# scrump.net
KiCad netlist of a schematic drawn in EAGLE
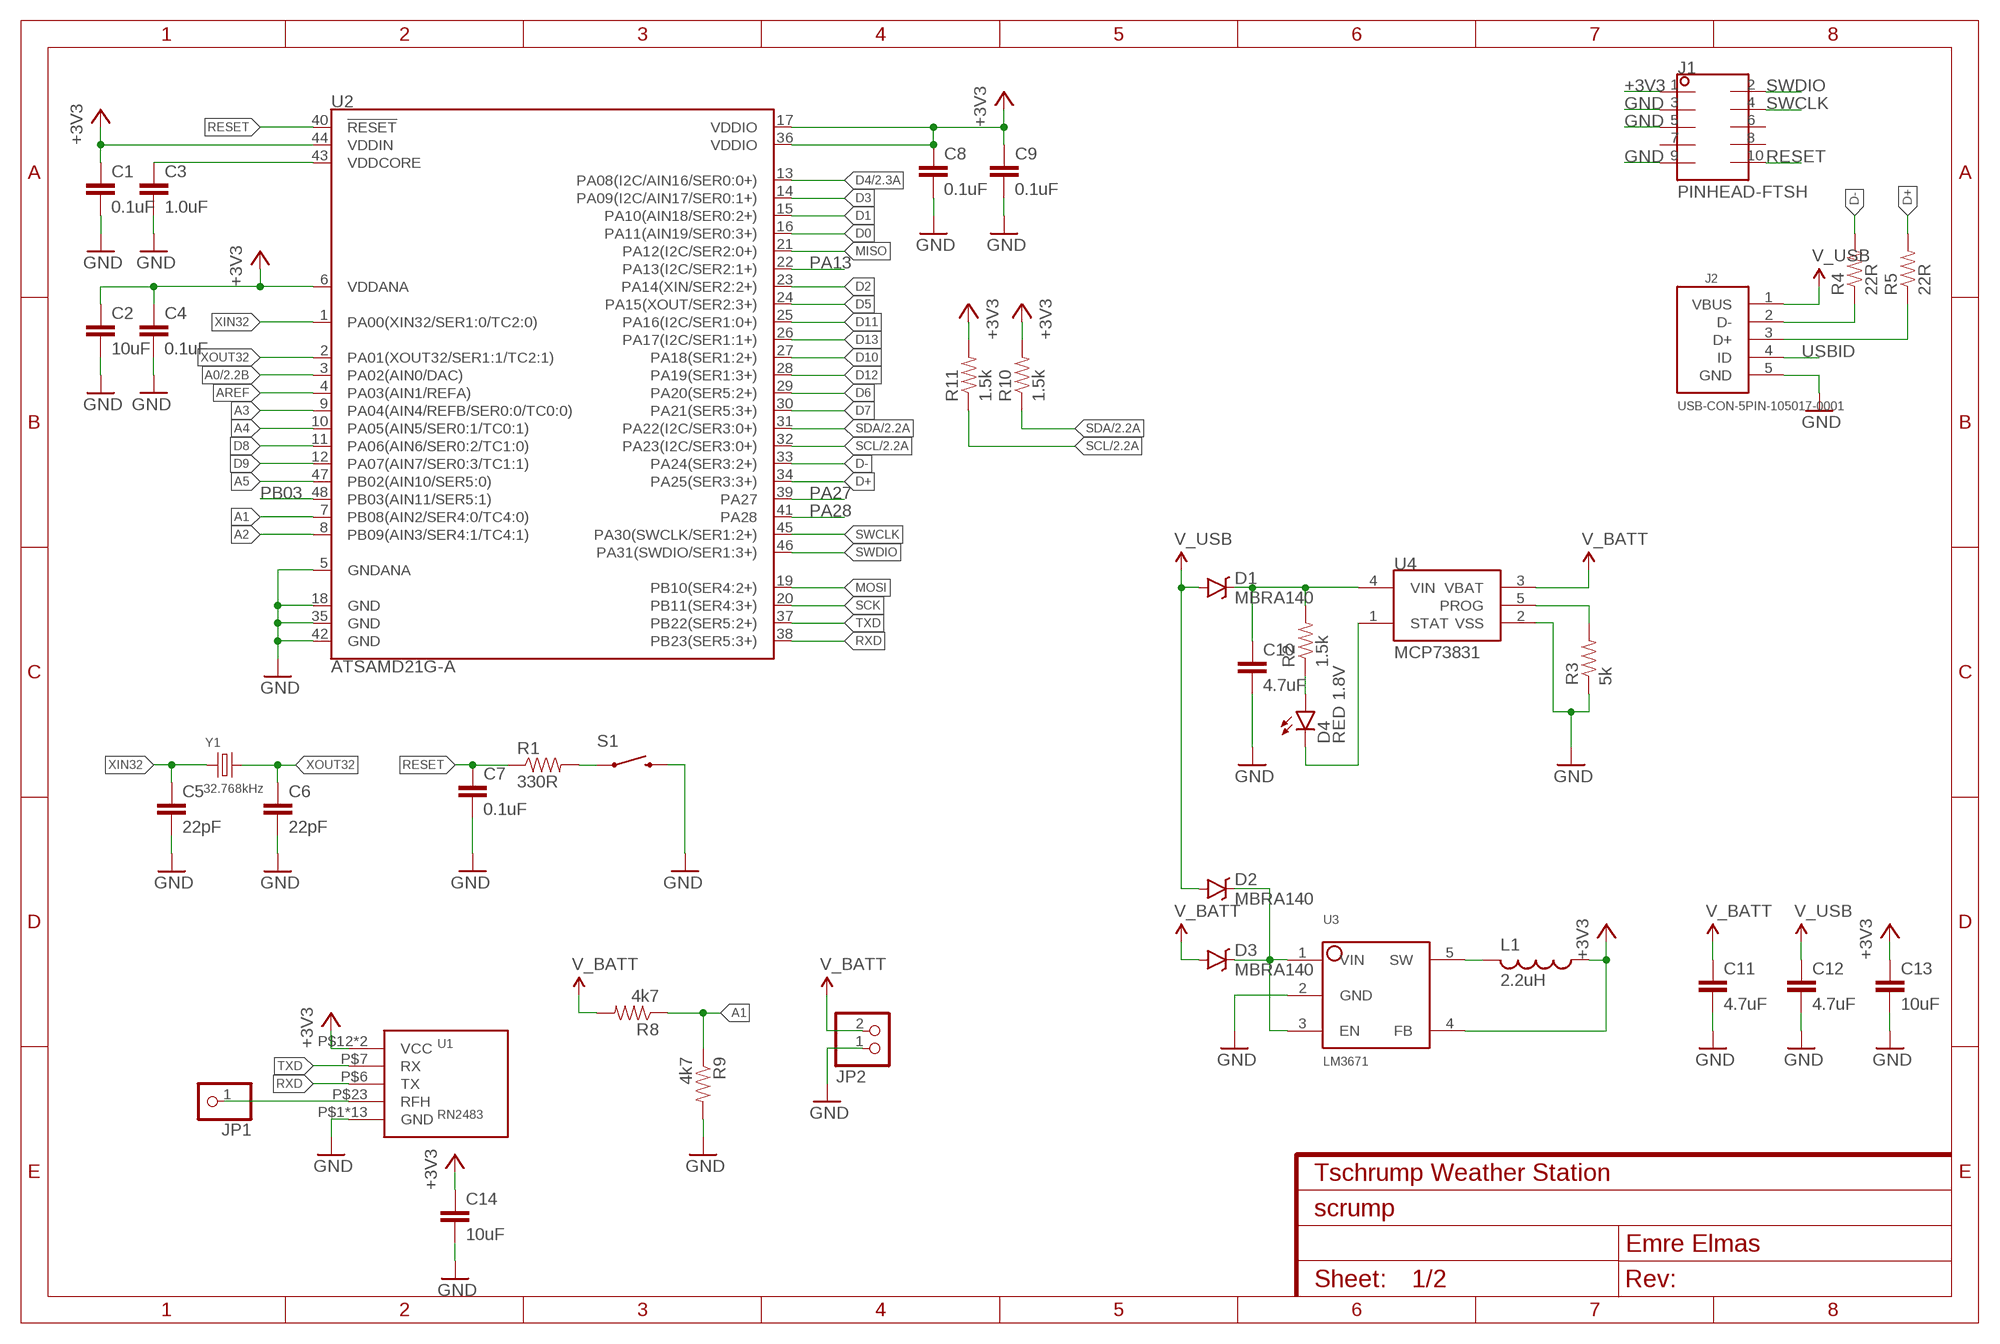
[diagram p0: schematic, sheet 1]
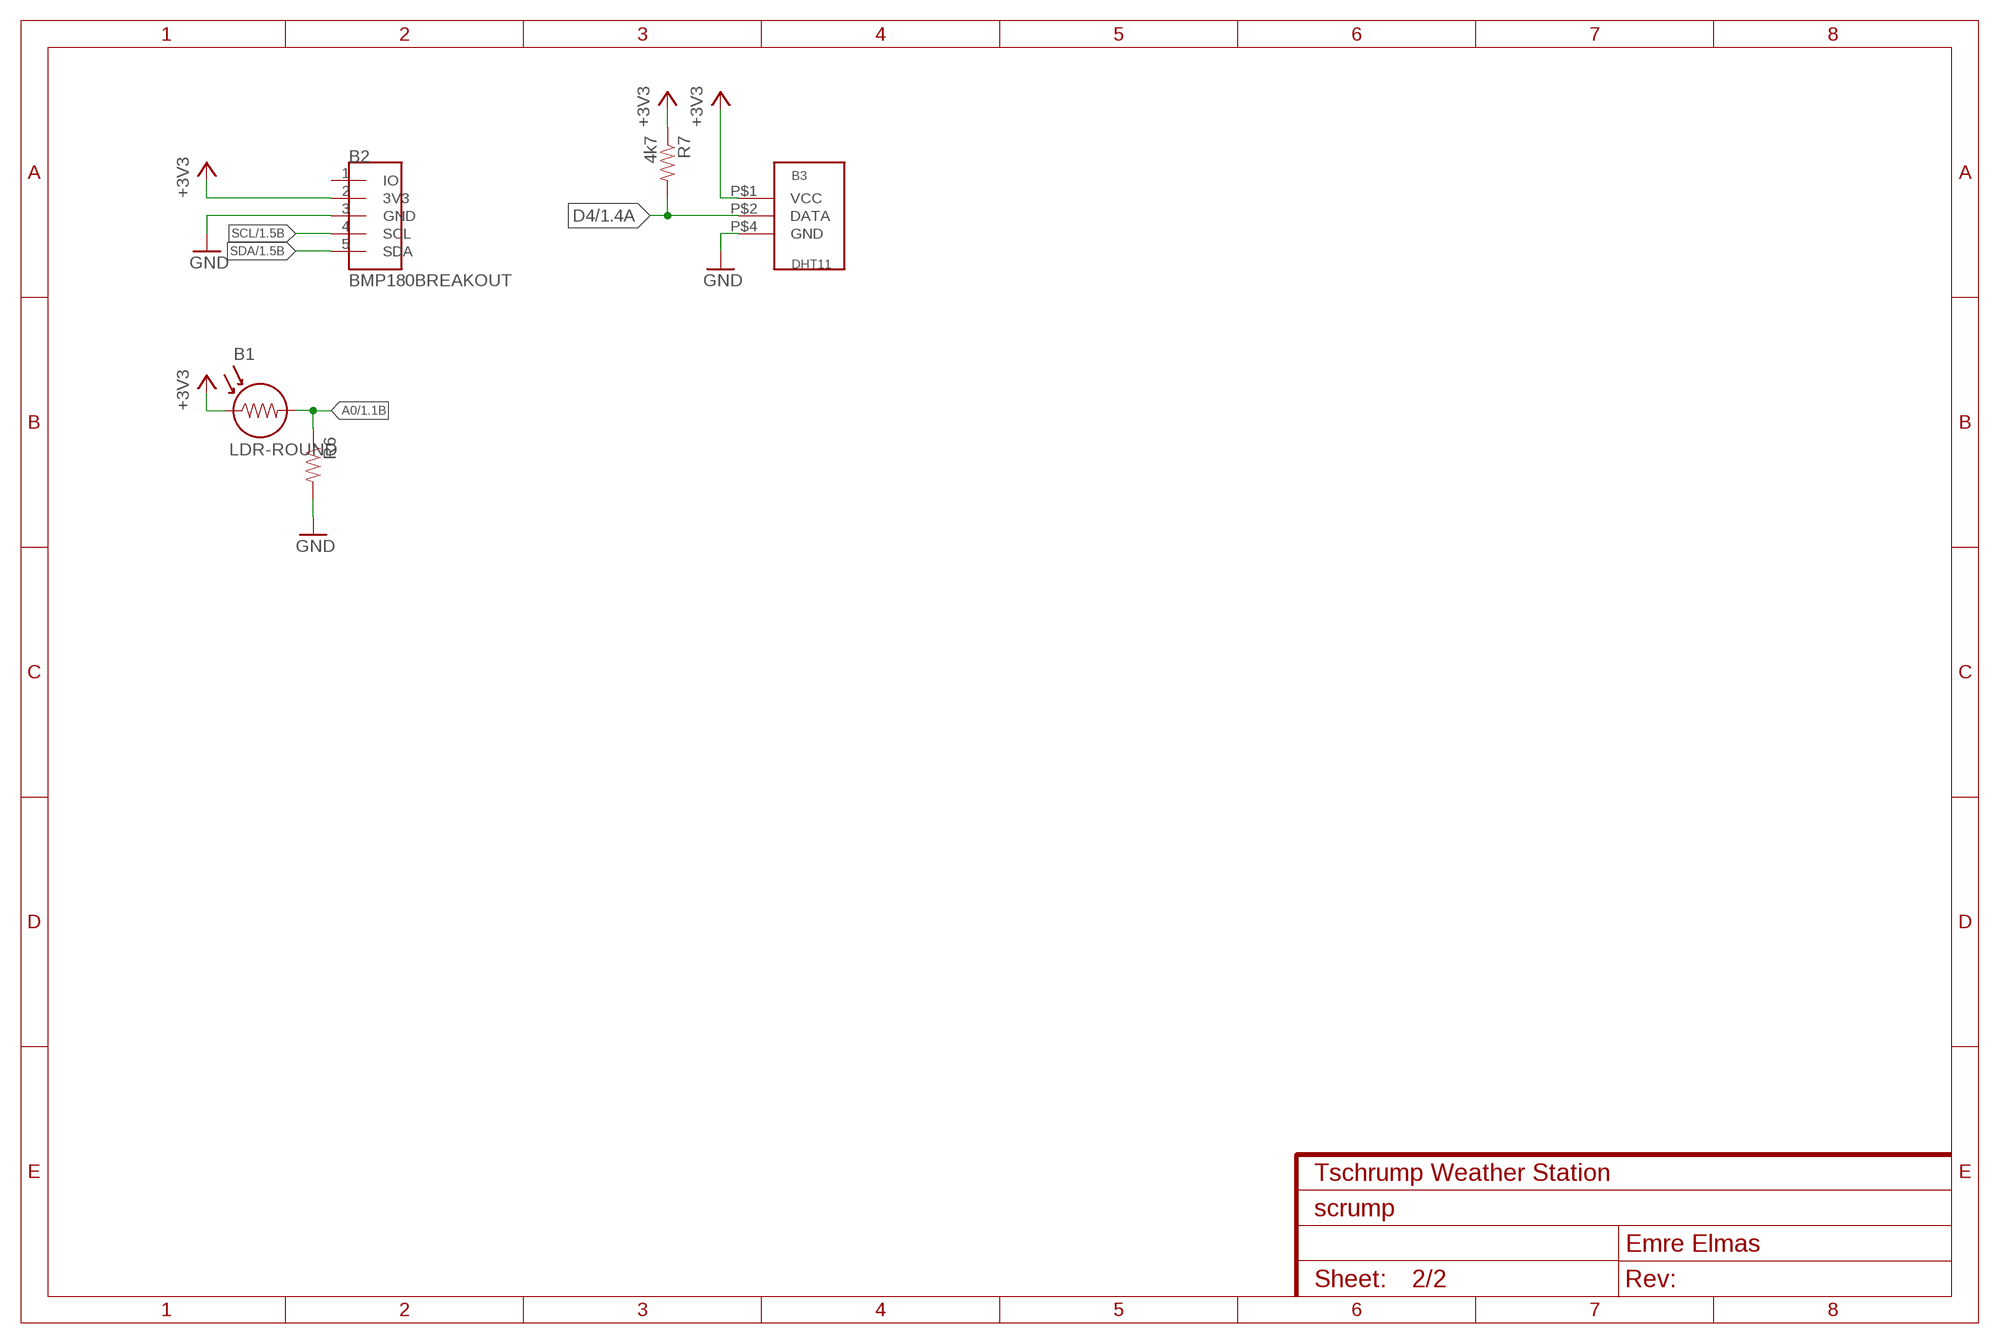
[diagram p1: schematic, sheet 2]

(export (version "E")
  (design (tool "Eeschema 10.0.6"))
  (components
    (comp (ref "B1")
      (value "LDR-ROUND")
      (footprint "eagle-import:LDR-ROUND")
      (libsource (lib "eagle-import") (part "LDR-ROUND"))
    )
    (comp (ref "B2")
      (value "BMP180BREAKOUT")
      (footprint "eagle-import:BMP180_BREAKOUT")
      (libsource (lib "eagle-import") (part "BMP180BREAKOUT"))
    )
    (comp (ref "B3")
      (value "DHT11")
      (footprint "eagle-import:DHT11")
      (libsource (lib "eagle-import") (part "DHT11"))
    )
    (comp (ref "R6")
      (value "RESISTOR0603")
      (footprint "eagle-import:0603-RES")
      (libsource (lib "eagle-import") (part "RESISTOR0603"))
    )
    (comp (ref "R7")
      (value "4k7")
      (footprint "eagle-import:0603-RES")
      (libsource (lib "eagle-import") (part "RESISTOR0603"))
    )
    (comp (ref "C1")
      (value "0.1uF")
      (footprint "eagle-import:0603-CAP")
      (libsource (lib "eagle-import") (part "CAP0603-CAP"))
    )
    (comp (ref "C2")
      (value "10uF")
      (footprint "eagle-import:0603-CAP")
      (libsource (lib "eagle-import") (part "CAP0603-CAP"))
    )
    (comp (ref "C3")
      (value "1.0uF")
      (footprint "eagle-import:0603-CAP")
      (libsource (lib "eagle-import") (part "CAP0603-CAP"))
    )
    (comp (ref "C4")
      (value "0.1uF")
      (footprint "eagle-import:0603-CAP")
      (libsource (lib "eagle-import") (part "CAP0603-CAP"))
    )
    (comp (ref "C5")
      (value "22pF")
      (footprint "eagle-import:0603-CAP")
      (libsource (lib "eagle-import") (part "CAP0603-CAP"))
    )
    (comp (ref "C6")
      (value "22pF")
      (footprint "eagle-import:0603-CAP")
      (libsource (lib "eagle-import") (part "CAP0603-CAP"))
    )
    (comp (ref "C7")
      (value "0.1uF")
      (footprint "eagle-import:0603-CAP")
      (libsource (lib "eagle-import") (part "0.1UF-25V(+80/-20%)(0603)"))
    )
    (comp (ref "C8")
      (value "0.1uF")
      (footprint "eagle-import:0603-CAP")
      (libsource (lib "eagle-import") (part "CAP0603-CAP"))
    )
    (comp (ref "C9")
      (value "0.1uF")
      (footprint "eagle-import:0603-CAP")
      (libsource (lib "eagle-import") (part "CAP0603-CAP"))
    )
    (comp (ref "C10")
      (value "4.7uF")
      (footprint "eagle-import:0603-CAP")
      (libsource (lib "eagle-import") (part "CAP0603-CAP"))
    )
    (comp (ref "C11")
      (value "4.7uF")
      (footprint "eagle-import:0603-CAP")
      (libsource (lib "eagle-import") (part "CAP0603-CAP"))
    )
    (comp (ref "C12")
      (value "4.7uF")
      (footprint "eagle-import:0603-CAP")
      (libsource (lib "eagle-import") (part "CAP0603-CAP"))
    )
    (comp (ref "C13")
      (value "10uF")
      (footprint "eagle-import:0603-CAP")
      (libsource (lib "eagle-import") (part "CAP0603-CAP"))
    )
    (comp (ref "C14")
      (value "10uF")
      (footprint "eagle-import:0603-CAP")
      (libsource (lib "eagle-import") (part "CAP0603-CAP"))
    )
    (comp (ref "D1")
      (value "MBRA140")
      (footprint "eagle-import:SMA-DIODE")
      (libsource (lib "eagle-import") (part "MBRA140"))
    )
    (comp (ref "D2")
      (value "MBRA140")
      (footprint "eagle-import:SMA-DIODE")
      (libsource (lib "eagle-import") (part "MBRA140"))
    )
    (comp (ref "D3")
      (value "MBRA140")
      (footprint "eagle-import:SMA-DIODE")
      (libsource (lib "eagle-import") (part "MBRA140"))
    )
    (comp (ref "D4")
      (value "RED 1.8V")
      (footprint "eagle-import:LED-0603")
      (libsource (lib "eagle-import") (part "LED-RED0603"))
    )
    (comp (ref "J1")
      (value "PINHEAD-FTSH")
      (footprint "eagle-import:FTSH-105-01-XXX-DV-K")
      (libsource (lib "eagle-import") (part "PINHEAD-FTSH"))
    )
    (comp (ref "J2")
      (value "USB-CON-5PIN-105017-0001")
      (footprint "eagle-import:USB-MICRO-MOLEX-105017-0001")
      (libsource (lib "eagle-import") (part "USB-CON-5PIN-105017-0001"))
    )
    (comp (ref "JP1")
      (value "PINHD-1X1")
      (footprint "eagle-import:1X01")
      (libsource (lib "eagle-import") (part "PINHD-1X1"))
    )
    (comp (ref "JP2")
      (value "PINHD-1X2")
      (footprint "eagle-import:1X02")
      (libsource (lib "eagle-import") (part "PINHD-1X2"))
    )
    (comp (ref "L1")
      (value "2.2uH")
      (footprint "eagle-import:0806-INDUCTOR")
      (libsource (lib "eagle-import") (part "INDUCTOR"))
    )
    (comp (ref "R1")
      (value "330R")
      (footprint "eagle-import:0603-RES")
      (libsource (lib "eagle-import") (part "RESISTOR0603"))
    )
    (comp (ref "R2")
      (value "1.5k")
      (footprint "eagle-import:0603-RES")
      (libsource (lib "eagle-import") (part "RESISTOR0603"))
    )
    (comp (ref "R3")
      (value "5k")
      (footprint "eagle-import:0603-RES")
      (libsource (lib "eagle-import") (part "RESISTOR0603"))
    )
    (comp (ref "R4")
      (value "22R")
      (footprint "eagle-import:0603-RES")
      (libsource (lib "eagle-import") (part "RESISTOR0603"))
    )
    (comp (ref "R5")
      (value "22R")
      (footprint "eagle-import:0603-RES")
      (libsource (lib "eagle-import") (part "RESISTOR0603"))
    )
    (comp (ref "R8")
      (value "4k7")
      (footprint "eagle-import:0603-RES")
      (libsource (lib "eagle-import") (part "RESISTOR0603"))
    )
    (comp (ref "R9")
      (value "4k7")
      (footprint "eagle-import:0603-RES")
      (libsource (lib "eagle-import") (part "RESISTOR0603"))
    )
    (comp (ref "R10")
      (value "1.5k")
      (footprint "eagle-import:0603-RES")
      (libsource (lib "eagle-import") (part "RESISTOR0603"))
    )
    (comp (ref "R11")
      (value "1.5k")
      (footprint "eagle-import:0603-RES")
      (libsource (lib "eagle-import") (part "RESISTOR0603"))
    )
    (comp (ref "S1")
      (value "PUSHBUTTON-SMD")
      (footprint "eagle-import:TACTILE-SMD-SWITCH")
      (libsource (lib "eagle-import") (part "PUSHBUTTON-SMD"))
    )
    (comp (ref "U1")
      (value "RN2483")
      (footprint "eagle-import:RN2483")
      (libsource (lib "eagle-import") (part "RN2483"))
    )
    (comp (ref "U2")
      (value "ATSAMD21G-A")
      (footprint "eagle-import:TQFP-48")
      (libsource (lib "eagle-import") (part "ATSAMD21G-A"))
    )
    (comp (ref "U3")
      (value "LM3671")
      (footprint "eagle-import:SOT23-5")
      (libsource (lib "eagle-import") (part "LM3671"))
    )
    (comp (ref "U4")
      (value "MCP73831")
      (footprint "eagle-import:SOT23-5")
      (libsource (lib "eagle-import") (part "MCP73831"))
    )
    (comp (ref "Y1")
      (value "32.768kHz")
      (footprint "eagle-import:ABS25")
      (libsource (lib "eagle-import") (part "CRYSTAL"))
    )
  )
  (nets
    (net (code "1") (name "+3V3") (class "Default")
      (node (ref "B1") (pin "P$1") (pinfunction "1_P$1") (pintype "passive"))
      (node (ref "B2") (pin "2") (pinfunction "3V3_2") (pintype "bidirectional"))
      (node (ref "B3") (pin "P$1") (pinfunction "VCC_P$1") (pintype "bidirectional"))
      (node (ref "C1") (pin "1") (pinfunction "1_1") (pintype "passive"))
      (node (ref "C13") (pin "1") (pinfunction "1_1") (pintype "passive"))
      (node (ref "C14") (pin "1") (pinfunction "1_1") (pintype "passive"))
      (node (ref "C2") (pin "1") (pinfunction "1_1") (pintype "passive"))
      (node (ref "C4") (pin "1") (pinfunction "1_1") (pintype "passive"))
      (node (ref "C8") (pin "1") (pinfunction "1_1") (pintype "passive"))
      (node (ref "C9") (pin "1") (pinfunction "1_1") (pintype "passive"))
      (node (ref "J1") (pin "1") (pinfunction "P$1_1") (pintype "bidirectional"))
      (node (ref "L1") (pin "1") (pinfunction "1_1") (pintype "passive"))
      (node (ref "R10") (pin "2") (pinfunction "2_2") (pintype "passive"))
      (node (ref "R11") (pin "2") (pinfunction "2_2") (pintype "passive"))
      (node (ref "R7") (pin "1") (pinfunction "1_1") (pintype "passive"))
      (node (ref "U1") (pin "P$12") (pinfunction "VCC_P$12") (pintype "bidirectional"))
      (node (ref "U1") (pin "P$34") (pinfunction "VCC_P$34") (pintype "bidirectional"))
      (node (ref "U2") (pin "17") (pinfunction "VDDIO_17") (pintype "bidirectional"))
      (node (ref "U2") (pin "36") (pinfunction "VDDIO_36") (pintype "bidirectional"))
      (node (ref "U2") (pin "44") (pinfunction "VDDIN_44") (pintype "bidirectional"))
      (node (ref "U2") (pin "6") (pinfunction "VDDANA_6") (pintype "bidirectional"))
      (node (ref "U3") (pin "4") (pinfunction "FB_4") (pintype "bidirectional"))
    )
    (net (code "2") (name "A0") (class "Default")
      (node (ref "B1") (pin "P$2") (pinfunction "2_P$2") (pintype "passive"))
      (node (ref "R6") (pin "1") (pinfunction "1_1") (pintype "passive"))
      (node (ref "U2") (pin "3") (pinfunction "PA02(AIN0/DAC)_3") (pintype "bidirectional"))
    )
    (net (code "3") (name "A1") (class "Default")
      (node (ref "R8") (pin "1") (pinfunction "1_1") (pintype "passive"))
      (node (ref "R9") (pin "1") (pinfunction "1_1") (pintype "passive"))
      (node (ref "U2") (pin "7") (pinfunction "PB08(AIN2/SER4:0/TC4:0)_7") (pintype "bidirectional"))
    )
    (net (code "4") (name "A2") (class "Default")
      (node (ref "U2") (pin "8") (pinfunction "PB09(AIN3/SER4:1/TC4:1)_8") (pintype "bidirectional"))
    )
    (net (code "5") (name "A3") (class "Default")
      (node (ref "U2") (pin "9") (pinfunction "PA04(AIN4/REFB/SER0:0/TC0:0)_9") (pintype "bidirectional"))
    )
    (net (code "6") (name "A4") (class "Default")
      (node (ref "U2") (pin "10") (pinfunction "PA05(AIN5/SER0:1/TC0:1)_10") (pintype "bidirectional"))
    )
    (net (code "7") (name "A5") (class "Default")
      (node (ref "U2") (pin "47") (pinfunction "PB02(AIN10/SER5:0)_47") (pintype "bidirectional"))
    )
    (net (code "8") (name "AREF") (class "Default")
      (node (ref "U2") (pin "4") (pinfunction "PA03(AIN1/REFA)_4") (pintype "bidirectional"))
    )
    (net (code "9") (name "D+") (class "Default")
      (node (ref "R5") (pin "2") (pinfunction "2_2") (pintype "passive"))
      (node (ref "U2") (pin "34") (pinfunction "PA25(SER3:3+)_34") (pintype "bidirectional"))
    )
    (net (code "10") (name "D-") (class "Default")
      (node (ref "R4") (pin "2") (pinfunction "2_2") (pintype "passive"))
      (node (ref "U2") (pin "33") (pinfunction "PA24(SER3:2+)_33") (pintype "bidirectional"))
    )
    (net (code "11") (name "D0") (class "Default")
      (node (ref "U2") (pin "16") (pinfunction "PA11(AIN19/SER0:3+)_16") (pintype "bidirectional"))
    )
    (net (code "12") (name "D1") (class "Default")
      (node (ref "U2") (pin "15") (pinfunction "PA10(AIN18/SER0:2+)_15") (pintype "bidirectional"))
    )
    (net (code "13") (name "D2") (class "Default")
      (node (ref "U2") (pin "23") (pinfunction "PA14(XIN/SER2:2+)_23") (pintype "bidirectional"))
    )
    (net (code "14") (name "D3") (class "Default")
      (node (ref "U2") (pin "14") (pinfunction "PA09(I2C/AIN17/SER0:1+)_14") (pintype "bidirectional"))
    )
    (net (code "15") (name "D4") (class "Default")
      (node (ref "B3") (pin "P$2") (pinfunction "DATA_P$2") (pintype "bidirectional"))
      (node (ref "R7") (pin "2") (pinfunction "2_2") (pintype "passive"))
      (node (ref "U2") (pin "13") (pinfunction "PA08(I2C/AIN16/SER0:0+)_13") (pintype "bidirectional"))
    )
    (net (code "16") (name "D5") (class "Default")
      (node (ref "U2") (pin "24") (pinfunction "PA15(XOUT/SER2:3+)_24") (pintype "bidirectional"))
    )
    (net (code "17") (name "D6") (class "Default")
      (node (ref "U2") (pin "29") (pinfunction "PA20(SER5:2+)_29") (pintype "bidirectional"))
    )
    (net (code "18") (name "D7") (class "Default")
      (node (ref "U2") (pin "30") (pinfunction "PA21(SER5:3+)_30") (pintype "bidirectional"))
    )
    (net (code "19") (name "D8") (class "Default")
      (node (ref "U2") (pin "11") (pinfunction "PA06(AIN6/SER0:2/TC1:0)_11") (pintype "bidirectional"))
    )
    (net (code "20") (name "D9") (class "Default")
      (node (ref "U2") (pin "12") (pinfunction "PA07(AIN7/SER0:3/TC1:1)_12") (pintype "bidirectional"))
    )
    (net (code "21") (name "D10") (class "Default")
      (node (ref "U2") (pin "27") (pinfunction "PA18(SER1:2+)_27") (pintype "bidirectional"))
    )
    (net (code "22") (name "D11") (class "Default")
      (node (ref "U2") (pin "25") (pinfunction "PA16(I2C/SER1:0+)_25") (pintype "bidirectional"))
    )
    (net (code "23") (name "D12") (class "Default")
      (node (ref "U2") (pin "28") (pinfunction "PA19(SER1:3+)_28") (pintype "bidirectional"))
    )
    (net (code "24") (name "D13") (class "Default")
      (node (ref "U2") (pin "26") (pinfunction "PA17(I2C/SER1:1+)_26") (pintype "bidirectional"))
    )
    (net (code "25") (name "GND") (class "Default")
      (node (ref "B2") (pin "3") (pinfunction "GND_3") (pintype "bidirectional"))
      (node (ref "B3") (pin "P$4") (pinfunction "GND_P$4") (pintype "bidirectional"))
      (node (ref "C1") (pin "2") (pinfunction "2_2") (pintype "passive"))
      (node (ref "C10") (pin "2") (pinfunction "2_2") (pintype "passive"))
      (node (ref "C11") (pin "2") (pinfunction "2_2") (pintype "passive"))
      (node (ref "C12") (pin "2") (pinfunction "2_2") (pintype "passive"))
      (node (ref "C13") (pin "2") (pinfunction "2_2") (pintype "passive"))
      (node (ref "C14") (pin "2") (pinfunction "2_2") (pintype "passive"))
      (node (ref "C2") (pin "2") (pinfunction "2_2") (pintype "passive"))
      (node (ref "C3") (pin "2") (pinfunction "2_2") (pintype "passive"))
      (node (ref "C4") (pin "2") (pinfunction "2_2") (pintype "passive"))
      (node (ref "C5") (pin "2") (pinfunction "2_2") (pintype "passive"))
      (node (ref "C6") (pin "2") (pinfunction "2_2") (pintype "passive"))
      (node (ref "C7") (pin "2") (pinfunction "2_2") (pintype "passive"))
      (node (ref "C8") (pin "2") (pinfunction "2_2") (pintype "passive"))
      (node (ref "C9") (pin "2") (pinfunction "2_2") (pintype "passive"))
      (node (ref "J1") (pin "3") (pinfunction "P$3_3") (pintype "bidirectional"))
      (node (ref "J1") (pin "5") (pinfunction "P$5_5") (pintype "bidirectional"))
      (node (ref "J1") (pin "9") (pinfunction "P$9_9") (pintype "bidirectional"))
      (node (ref "J2") (pin "5") (pinfunction "GND_5") (pintype "power_in"))
      (node (ref "JP2") (pin "1") (pinfunction "1_1") (pintype "passive"))
      (node (ref "R3") (pin "1") (pinfunction "1_1") (pintype "passive"))
      (node (ref "R6") (pin "2") (pinfunction "2_2") (pintype "passive"))
      (node (ref "R9") (pin "2") (pinfunction "2_2") (pintype "passive"))
      (node (ref "S1") (pin "P$3") (pinfunction "2_P$3") (pintype "passive"))
      (node (ref "S1") (pin "P$4") (pinfunction "2_P$4") (pintype "passive"))
      (node (ref "U1") (pin "P$1") (pinfunction "GND_P$1") (pintype "bidirectional"))
      (node (ref "U1") (pin "P$11") (pinfunction "GND_P$11") (pintype "bidirectional"))
      (node (ref "U1") (pin "P$20") (pinfunction "GND_P$20") (pintype "bidirectional"))
      (node (ref "U1") (pin "P$21") (pinfunction "GND_P$21") (pintype "bidirectional"))
      (node (ref "U1") (pin "P$22") (pinfunction "GND_P$22") (pintype "bidirectional"))
      (node (ref "U1") (pin "P$24") (pinfunction "GND_P$24") (pintype "bidirectional"))
      (node (ref "U1") (pin "P$26") (pinfunction "GND_P$26") (pintype "bidirectional"))
      (node (ref "U1") (pin "P$27") (pinfunction "GND_P$27") (pintype "bidirectional"))
      (node (ref "U1") (pin "P$28") (pinfunction "GND_P$28") (pintype "bidirectional"))
      (node (ref "U1") (pin "P$33") (pinfunction "GND_P$33") (pintype "bidirectional"))
      (node (ref "U1") (pin "P$41") (pinfunction "GND_P$41") (pintype "bidirectional"))
      (node (ref "U1") (pin "P$47") (pinfunction "GND_P$47") (pintype "bidirectional"))
      (node (ref "U1") (pin "P$8") (pinfunction "GND_P$8") (pintype "bidirectional"))
      (node (ref "U2") (pin "18") (pinfunction "GND_18") (pintype "bidirectional"))
      (node (ref "U2") (pin "35") (pinfunction "GND_35") (pintype "bidirectional"))
      (node (ref "U2") (pin "42") (pinfunction "GND_42") (pintype "bidirectional"))
      (node (ref "U2") (pin "5") (pinfunction "GNDANA_5") (pintype "bidirectional"))
      (node (ref "U3") (pin "2") (pinfunction "GND_2") (pintype "bidirectional"))
      (node (ref "U4") (pin "2") (pinfunction "VSS_2") (pintype "bidirectional"))
    )
    (net (code "26") (name "MISO") (class "Default")
      (node (ref "U2") (pin "21") (pinfunction "PA12(I2C/SER2:0+)_21") (pintype "bidirectional"))
    )
    (net (code "27") (name "MOSI") (class "Default")
      (node (ref "U2") (pin "19") (pinfunction "PB10(SER4:2+)_19") (pintype "bidirectional"))
    )
    (net (code "28") (name "Net-(D4-PadA)") (class "Default")
      (node (ref "D4") (pin "A") (pinfunction "A_A") (pintype "passive"))
      (node (ref "R2") (pin "1") (pinfunction "1_1") (pintype "passive"))
    )
    (net (code "29") (name "Net-(J2-D+)") (class "Default")
      (node (ref "J2") (pin "3") (pinfunction "D+_3") (pintype "bidirectional"))
      (node (ref "R5") (pin "1") (pinfunction "1_1") (pintype "passive"))
    )
    (net (code "30") (name "Net-(J2-D-)") (class "Default")
      (node (ref "J2") (pin "2") (pinfunction "D-_2") (pintype "bidirectional"))
      (node (ref "R4") (pin "1") (pinfunction "1_1") (pintype "passive"))
    )
    (net (code "31") (name "Net-(R1-Pad2)") (class "Default")
      (node (ref "R1") (pin "2") (pinfunction "2_2") (pintype "passive"))
      (node (ref "S1") (pin "P$1") (pinfunction "1_P$1") (pintype "passive"))
      (node (ref "S1") (pin "P$2") (pinfunction "1_P$2") (pintype "passive"))
    )
    (net (code "32") (name "Net-(U1-RFH)") (class "Default")
      (node (ref "JP1") (pin "1") (pinfunction "1_1") (pintype "passive"))
      (node (ref "U1") (pin "P$23") (pinfunction "RFH_P$23") (pintype "bidirectional"))
    )
    (net (code "33") (name "Net-(U2-VDDCORE)") (class "Default")
      (node (ref "C3") (pin "1") (pinfunction "1_1") (pintype "passive"))
      (node (ref "U2") (pin "43") (pinfunction "VDDCORE_43") (pintype "bidirectional"))
    )
    (net (code "34") (name "Net-(U3-EN)") (class "Default")
      (node (ref "D2") (pin "C") (pinfunction "C_C") (pintype "passive"))
      (node (ref "D3") (pin "C") (pinfunction "C_C") (pintype "passive"))
      (node (ref "U3") (pin "1") (pinfunction "VIN_1") (pintype "bidirectional"))
      (node (ref "U3") (pin "3") (pinfunction "EN_3") (pintype "bidirectional"))
    )
    (net (code "35") (name "Net-(U3-SW)") (class "Default")
      (node (ref "L1") (pin "2") (pinfunction "2_2") (pintype "passive"))
      (node (ref "U3") (pin "5") (pinfunction "SW_5") (pintype "bidirectional"))
    )
    (net (code "36") (name "Net-(U4-PROG)") (class "Default")
      (node (ref "R3") (pin "2") (pinfunction "2_2") (pintype "passive"))
      (node (ref "U4") (pin "5") (pinfunction "PROG_5") (pintype "bidirectional"))
    )
    (net (code "37") (name "Net-(U4-STAT)") (class "Default")
      (node (ref "D4") (pin "C") (pinfunction "C_C") (pintype "passive"))
      (node (ref "U4") (pin "1") (pinfunction "STAT_1") (pintype "bidirectional"))
    )
    (net (code "38") (name "Net-(U4-VIN)") (class "Default")
      (node (ref "C10") (pin "1") (pinfunction "1_1") (pintype "passive"))
      (node (ref "D1") (pin "C") (pinfunction "C_C") (pintype "passive"))
      (node (ref "R2") (pin "2") (pinfunction "2_2") (pintype "passive"))
      (node (ref "U4") (pin "4") (pinfunction "VIN_4") (pintype "bidirectional"))
    )
    (net (code "39") (name "PA13") (class "Default")
      (node (ref "U2") (pin "22") (pinfunction "PA13(I2C/SER2:1+)_22") (pintype "bidirectional"))
    )
    (net (code "40") (name "PA27") (class "Default")
      (node (ref "U2") (pin "39") (pinfunction "PA27_39") (pintype "bidirectional"))
    )
    (net (code "41") (name "PA28") (class "Default")
      (node (ref "U2") (pin "41") (pinfunction "PA28_41") (pintype "bidirectional"))
    )
    (net (code "42") (name "PB03") (class "Default")
      (node (ref "U2") (pin "48") (pinfunction "PB03(AIN11/SER5:1)_48") (pintype "bidirectional"))
    )
    (net (code "43") (name "RESET") (class "Default")
      (node (ref "C7") (pin "1") (pinfunction "1_1") (pintype "passive"))
      (node (ref "J1") (pin "10") (pinfunction "P$10_10") (pintype "bidirectional"))
      (node (ref "R1") (pin "1") (pinfunction "1_1") (pintype "passive"))
      (node (ref "U2") (pin "40") (pinfunction "~{RESET}_40") (pintype "bidirectional"))
    )
    (net (code "44") (name "RXD") (class "Default")
      (node (ref "U1") (pin "P$6") (pinfunction "TX_P$6") (pintype "bidirectional"))
      (node (ref "U2") (pin "38") (pinfunction "PB23(SER5:3+)_38") (pintype "bidirectional"))
    )
    (net (code "45") (name "SCK") (class "Default")
      (node (ref "U2") (pin "20") (pinfunction "PB11(SER4:3+)_20") (pintype "bidirectional"))
    )
    (net (code "46") (name "SCL") (class "Default")
      (node (ref "B2") (pin "4") (pinfunction "SCL_4") (pintype "bidirectional"))
      (node (ref "R11") (pin "1") (pinfunction "1_1") (pintype "passive"))
      (node (ref "U2") (pin "32") (pinfunction "PA23(I2C/SER3:0+)_32") (pintype "bidirectional"))
    )
    (net (code "47") (name "SDA") (class "Default")
      (node (ref "B2") (pin "5") (pinfunction "SDA_5") (pintype "bidirectional"))
      (node (ref "R10") (pin "1") (pinfunction "1_1") (pintype "passive"))
      (node (ref "U2") (pin "31") (pinfunction "PA22(I2C/SER3:0+)_31") (pintype "bidirectional"))
    )
    (net (code "48") (name "SWCLK") (class "Default")
      (node (ref "J1") (pin "4") (pinfunction "P$4_4") (pintype "bidirectional"))
      (node (ref "U2") (pin "45") (pinfunction "PA30(SWCLK/SER1:2+)_45") (pintype "bidirectional"))
    )
    (net (code "49") (name "SWDIO") (class "Default")
      (node (ref "J1") (pin "2") (pinfunction "P$2_2") (pintype "bidirectional"))
      (node (ref "U2") (pin "46") (pinfunction "PA31(SWDIO/SER1:3+)_46") (pintype "bidirectional"))
    )
    (net (code "50") (name "TXD") (class "Default")
      (node (ref "U1") (pin "P$7") (pinfunction "RX_P$7") (pintype "bidirectional"))
      (node (ref "U2") (pin "37") (pinfunction "PB22(SER5:2+)_37") (pintype "bidirectional"))
    )
    (net (code "51") (name "USBID") (class "Default")
      (node (ref "J2") (pin "4") (pinfunction "ID_4") (pintype "bidirectional"))
    )
    (net (code "52") (name "V_BATT") (class "Default")
      (node (ref "C11") (pin "1") (pinfunction "1_1") (pintype "passive"))
      (node (ref "D3") (pin "A") (pinfunction "A_A") (pintype "passive"))
      (node (ref "JP2") (pin "2") (pinfunction "2_2") (pintype "passive"))
      (node (ref "R8") (pin "2") (pinfunction "2_2") (pintype "passive"))
      (node (ref "U4") (pin "3") (pinfunction "VBAT_3") (pintype "bidirectional"))
    )
    (net (code "53") (name "V_USB") (class "Default")
      (node (ref "C12") (pin "1") (pinfunction "1_1") (pintype "passive"))
      (node (ref "D1") (pin "A") (pinfunction "A_A") (pintype "passive"))
      (node (ref "D2") (pin "A") (pinfunction "A_A") (pintype "passive"))
      (node (ref "J2") (pin "1") (pinfunction "VBUS_1") (pintype "power_in"))
    )
    (net (code "54") (name "XIN32") (class "Default")
      (node (ref "C5") (pin "1") (pinfunction "1_1") (pintype "passive"))
      (node (ref "U2") (pin "1") (pinfunction "PA00(XIN32/SER1:0/TC2:0)_1") (pintype "bidirectional"))
      (node (ref "Y1") (pin "P$1") (pinfunction "1_P$1") (pintype "passive"))
    )
    (net (code "55") (name "XOUT32") (class "Default")
      (node (ref "C6") (pin "1") (pinfunction "1_1") (pintype "passive"))
      (node (ref "U2") (pin "2") (pinfunction "PA01(XOUT32/SER1:1/TC2:1)_2") (pintype "bidirectional"))
      (node (ref "Y1") (pin "P$4") (pinfunction "3_P$4") (pintype "passive"))
    )
    (net (code "56") (name "unconnected-(B2-IO-Pad1)") (class "Default")
      (node (ref "B2") (pin "1") (pinfunction "IO_1") (pintype "bidirectional"))
    )
    (net (code "57") (name "unconnected-(J1-P$6-Pad6)") (class "Default")
      (node (ref "J1") (pin "6") (pinfunction "P$6_6") (pintype "bidirectional"))
    )
    (net (code "58") (name "unconnected-(J1-P$7-Pad7)") (class "Default")
      (node (ref "J1") (pin "7") (pinfunction "P$7_7") (pintype "bidirectional"))
    )
    (net (code "59") (name "unconnected-(J1-P$8-Pad8)") (class "Default")
      (node (ref "J1") (pin "8") (pinfunction "P$8_8") (pintype "bidirectional"))
    )
  )
)
